# E77whistle.net
KiCad netlist of a schematic drawn in Altium Designer
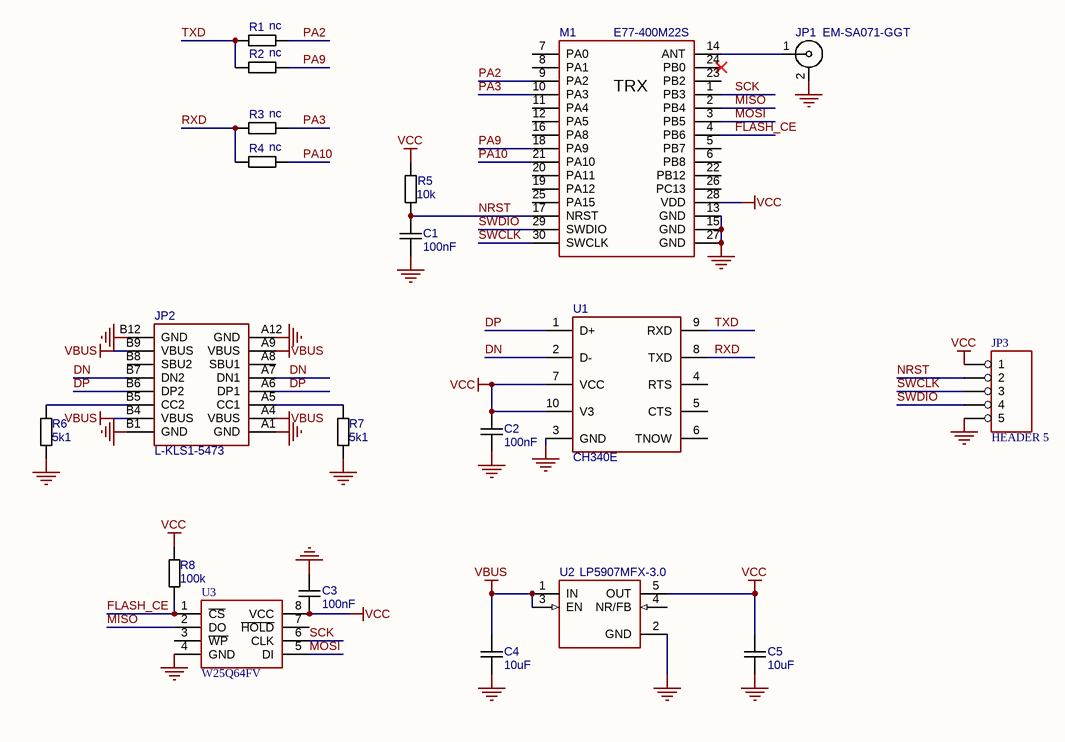
[diagram p0: E77whistle.SchDoc]

(export (version "E")
  (design (tool "Eeschema 10.0.6"))
  (components
    (comp (ref "C1")
      (value "100nF")
      (footprint "C-0603")
      (fields (field (name "VOLTAGE") "50V"))
      (libsource (lib "Passive") (part "CAPN"))
    )
    (comp (ref "C2")
      (value "100nF")
      (footprint "C-0603")
      (fields (field (name "VOLTAGE") "50V"))
      (libsource (lib "Passive") (part "CAPN"))
    )
    (comp (ref "C3")
      (value "100nF")
      (footprint "C-0603")
      (fields (field (name "VOLTAGE") "50V"))
      (libsource (lib "Passive") (part "CAPN"))
    )
    (comp (ref "C4")
      (value "10uF")
      (footprint "C-0805")
      (fields (field (name "VOLTAGE") "50V"))
      (libsource (lib "Passive") (part "CAPN"))
    )
    (comp (ref "C5")
      (value "10uF")
      (footprint "C-0805")
      (fields (field (name "VOLTAGE") "50V"))
      (libsource (lib "Passive") (part "CAPN"))
    )
    (comp (ref "JP1")
      (value "EM-SA071-GGT")
      (footprint "SMA_F_EDGE")
      (description "SMA Female R/A PCB Mount")
      (libsource (lib "Connectors") (part "SMA"))
    )
    (comp (ref "JP2")
      (value "L-KLS1-5473")
      (footprint "L-KLS1-5473")
      (libsource (lib "Connectors") (part "L-KLS1-5473"))
    )
    (comp (ref "JP3")
      (value "HEADER 5")
      (footprint "PLS1-5_SMD")
      (libsource (lib "Connectors") (part "HEADER 5"))
    )
    (comp (ref "M1")
      (value "E77-400M22S")
      (footprint "E77XX-M22")
      (libsource (lib "RFmodules") (part "E77-400M22S"))
    )
    (comp (ref "R1") (value "nc") (footprint "R-0603") (libsource (lib "Passive") (part "RES")))
    (comp (ref "R2") (value "nc") (footprint "R-0603") (libsource (lib "Passive") (part "RES")))
    (comp (ref "R3") (value "nc") (footprint "R-0603") (libsource (lib "Passive") (part "RES")))
    (comp (ref "R4") (value "nc") (footprint "R-0603") (libsource (lib "Passive") (part "RES")))
    (comp (ref "R5") (value "10k") (footprint "R-0603") (libsource (lib "") (part "RES_1")))
    (comp (ref "R6") (value "5k1") (footprint "R-0603") (libsource (lib "") (part "RES_2")))
    (comp (ref "R7") (value "5k1") (footprint "R-0603") (libsource (lib "") (part "RES_2")))
    (comp (ref "R8") (value "100k") (footprint "R-0603") (libsource (lib "") (part "RES_1")))
    (comp (ref "U1") (value "CH340E") (footprint "MSOP-10") (libsource (lib "ICs") (part "CH340E")))
    (comp (ref "U2")
      (value "LP5907MFX-3.0")
      (footprint "SOT-23-5")
      (description "250mA Low-Dropout Regulator")
      (libsource (lib "ICs") (part "LP5907"))
    )
    (comp (ref "U3") (value "W25Q64FV") (footprint "SO-8") (libsource (lib "ICs") (part "W25Q64FV")))
  )
  (nets
    (net (code "1") (name "/DN") (class "Default")
      (node (ref "JP2") (pin "A7") (pinfunction "DN1_A7") (pintype "passive"))
      (node (ref "JP2") (pin "B7") (pinfunction "DN2_B7") (pintype "passive"))
      (node (ref "U1") (pin "2") (pinfunction "D-_2") (pintype "passive"))
    )
    (net (code "2") (name "/DP") (class "Default")
      (node (ref "JP2") (pin "A6") (pinfunction "DP1_A6") (pintype "passive"))
      (node (ref "JP2") (pin "B6") (pinfunction "DP2_B6") (pintype "passive"))
      (node (ref "U1") (pin "1") (pinfunction "D+_1") (pintype "passive"))
    )
    (net (code "3") (name "/FLASH_CE") (class "Default")
      (node (ref "M1") (pin "4") (pinfunction "PB6_4") (pintype "passive"))
      (node (ref "R8") (pin "1") (pinfunction "1_1") (pintype "passive"))
      (node (ref "U3") (pin "1") (pinfunction "~{CS}_1") (pintype "passive"))
    )
    (net (code "4") (name "/MISO") (class "Default")
      (node (ref "M1") (pin "2") (pinfunction "PB4_2") (pintype "passive"))
      (node (ref "U3") (pin "2") (pinfunction "DO_2") (pintype "passive"))
    )
    (net (code "5") (name "/MOSI") (class "Default")
      (node (ref "M1") (pin "3") (pinfunction "PB5_3") (pintype "passive"))
      (node (ref "U3") (pin "5") (pinfunction "DI_5") (pintype "passive"))
    )
    (net (code "6") (name "/NRST") (class "Default")
      (node (ref "C1") (pin "2") (pinfunction "2_2") (pintype "passive"))
      (node (ref "JP3") (pin "2") (pinfunction "2_2") (pintype "passive"))
      (node (ref "M1") (pin "17") (pinfunction "NRST_17") (pintype "passive"))
      (node (ref "R5") (pin "1") (pinfunction "1_1") (pintype "passive"))
    )
    (net (code "7") (name "/PA2") (class "Default")
      (node (ref "M1") (pin "9") (pinfunction "PA2_9") (pintype "passive"))
      (node (ref "R1") (pin "1") (pinfunction "1_1") (pintype "passive"))
    )
    (net (code "8") (name "/PA3") (class "Default")
      (node (ref "M1") (pin "10") (pinfunction "PA3_10") (pintype "passive"))
      (node (ref "R3") (pin "1") (pinfunction "1_1") (pintype "passive"))
    )
    (net (code "9") (name "/PA9") (class "Default")
      (node (ref "M1") (pin "18") (pinfunction "PA9_18") (pintype "passive"))
      (node (ref "R2") (pin "1") (pinfunction "1_1") (pintype "passive"))
    )
    (net (code "10") (name "/PA10") (class "Default")
      (node (ref "M1") (pin "21") (pinfunction "PA10_21") (pintype "passive"))
      (node (ref "R4") (pin "1") (pinfunction "1_1") (pintype "passive"))
    )
    (net (code "11") (name "/RXD") (class "Default")
      (node (ref "R3") (pin "2") (pinfunction "2_2") (pintype "passive"))
      (node (ref "R4") (pin "2") (pinfunction "2_2") (pintype "passive"))
      (node (ref "U1") (pin "8") (pinfunction "TXD_8") (pintype "passive"))
    )
    (net (code "12") (name "/SCK") (class "Default")
      (node (ref "M1") (pin "1") (pinfunction "PB3_1") (pintype "passive"))
      (node (ref "U3") (pin "6") (pinfunction "CLK_6") (pintype "passive"))
    )
    (net (code "13") (name "/SWCLK") (class "Default")
      (node (ref "JP3") (pin "3") (pinfunction "3_3") (pintype "passive"))
      (node (ref "M1") (pin "30") (pinfunction "SWCLK_30") (pintype "passive"))
    )
    (net (code "14") (name "/SWDIO") (class "Default")
      (node (ref "JP3") (pin "4") (pinfunction "4_4") (pintype "passive"))
      (node (ref "M1") (pin "29") (pinfunction "SWDIO_29") (pintype "passive"))
    )
    (net (code "15") (name "/TXD") (class "Default")
      (node (ref "R1") (pin "2") (pinfunction "2_2") (pintype "passive"))
      (node (ref "R2") (pin "2") (pinfunction "2_2") (pintype "passive"))
      (node (ref "U1") (pin "9") (pinfunction "RXD_9") (pintype "passive"))
    )
    (net (code "16") (name "GND") (class "Default")
      (node (ref "C1") (pin "1") (pinfunction "1_1") (pintype "passive"))
      (node (ref "C2") (pin "1") (pinfunction "1_1") (pintype "passive"))
      (node (ref "C3") (pin "1") (pinfunction "1_1") (pintype "passive"))
      (node (ref "C4") (pin "2") (pinfunction "2_2") (pintype "passive"))
      (node (ref "C5") (pin "2") (pinfunction "2_2") (pintype "passive"))
      (node (ref "JP1") (pin "2") (pinfunction "2_2") (pintype "passive"))
      (node (ref "JP2") (pin "A1") (pinfunction "GND_A1") (pintype "passive"))
      (node (ref "JP2") (pin "A12") (pinfunction "GND_A12") (pintype "passive"))
      (node (ref "JP2") (pin "B1") (pinfunction "GND_B1") (pintype "passive"))
      (node (ref "JP2") (pin "B12") (pinfunction "GND_B12") (pintype "passive"))
      (node (ref "JP3") (pin "5") (pinfunction "5_5") (pintype "passive"))
      (node (ref "M1") (pin "13") (pinfunction "GND_13") (pintype "passive"))
      (node (ref "M1") (pin "15") (pinfunction "GND_15") (pintype "passive"))
      (node (ref "M1") (pin "27") (pinfunction "GND_27") (pintype "passive"))
      (node (ref "R6") (pin "2") (pinfunction "2_2") (pintype "passive"))
      (node (ref "R7") (pin "2") (pinfunction "2_2") (pintype "passive"))
      (node (ref "U1") (pin "3") (pinfunction "GND_3") (pintype "passive"))
      (node (ref "U2") (pin "2") (pinfunction "GND_2") (pintype "power_in"))
      (node (ref "U3") (pin "4") (pinfunction "GND_4") (pintype "passive"))
    )
    (net (code "17") (name "Net-(JP2-CC1)") (class "Default")
      (node (ref "JP2") (pin "A5") (pinfunction "CC1_A5") (pintype "passive"))
      (node (ref "R7") (pin "1") (pinfunction "1_1") (pintype "passive"))
    )
    (net (code "18") (name "Net-(JP2-CC2)") (class "Default")
      (node (ref "JP2") (pin "B5") (pinfunction "CC2_B5") (pintype "passive"))
      (node (ref "R6") (pin "1") (pinfunction "1_1") (pintype "passive"))
    )
    (net (code "19") (name "Net-(M1-ANT)") (class "Default")
      (node (ref "JP1") (pin "1") (pinfunction "1_1") (pintype "passive"))
      (node (ref "M1") (pin "14") (pinfunction "ANT_14") (pintype "passive"))
    )
    (net (code "20") (name "VBUS") (class "Default")
      (node (ref "C4") (pin "1") (pinfunction "1_1") (pintype "passive"))
      (node (ref "JP2") (pin "A4") (pinfunction "VBUS_A4") (pintype "passive"))
      (node (ref "JP2") (pin "A9") (pinfunction "VBUS_A9") (pintype "passive"))
      (node (ref "JP2") (pin "B4") (pinfunction "VBUS_B4") (pintype "passive"))
      (node (ref "JP2") (pin "B9") (pinfunction "VBUS_B9") (pintype "passive"))
      (node (ref "U2") (pin "1") (pinfunction "IN_1") (pintype "power_in"))
      (node (ref "U2") (pin "3") (pinfunction "EN_3") (pintype "input"))
    )
    (net (code "21") (name "VCC") (class "Default")
      (node (ref "C2") (pin "2") (pinfunction "2_2") (pintype "passive"))
      (node (ref "C3") (pin "2") (pinfunction "2_2") (pintype "passive"))
      (node (ref "C5") (pin "1") (pinfunction "1_1") (pintype "passive"))
      (node (ref "JP3") (pin "1") (pinfunction "1_1") (pintype "passive"))
      (node (ref "M1") (pin "28") (pinfunction "VDD_28") (pintype "passive"))
      (node (ref "R5") (pin "2") (pinfunction "2_2") (pintype "passive"))
      (node (ref "R8") (pin "2") (pinfunction "2_2") (pintype "passive"))
      (node (ref "U1") (pin "10") (pinfunction "V3_10") (pintype "passive"))
      (node (ref "U1") (pin "7") (pinfunction "VCC_7") (pintype "passive"))
      (node (ref "U2") (pin "5") (pinfunction "OUT_5") (pintype "power_in"))
      (node (ref "U3") (pin "8") (pinfunction "VCC_8") (pintype "passive"))
    )
    (net (code "22") (name "VSS") (class "Default")
      (node (ref "JP2") (pin "17") (pinfunction "VSS_17") (pintype "power_in"))
    )
    (net (code "23") (name "unconnected-(JP2-SBU1-PadA8)") (class "Default")
      (node (ref "JP2") (pin "A8") (pinfunction "SBU1_A8") (pintype "passive"))
    )
    (net (code "24") (name "unconnected-(JP2-SBU2-PadB8)") (class "Default")
      (node (ref "JP2") (pin "B8") (pinfunction "SBU2_B8") (pintype "passive"))
    )
    (net (code "25") (name "unconnected-(M1-PA0-Pad7)") (class "Default")
      (node (ref "M1") (pin "7") (pinfunction "PA0_7") (pintype "passive"))
    )
    (net (code "26") (name "unconnected-(M1-PA1-Pad8)") (class "Default")
      (node (ref "M1") (pin "8") (pinfunction "PA1_8") (pintype "passive"))
    )
    (net (code "27") (name "unconnected-(M1-PA4-Pad11)") (class "Default")
      (node (ref "M1") (pin "11") (pinfunction "PA4_11") (pintype "passive"))
    )
    (net (code "28") (name "unconnected-(M1-PA5-Pad12)") (class "Default")
      (node (ref "M1") (pin "12") (pinfunction "PA5_12") (pintype "passive"))
    )
    (net (code "29") (name "unconnected-(M1-PA8-Pad16)") (class "Default")
      (node (ref "M1") (pin "16") (pinfunction "PA8_16") (pintype "passive"))
    )
    (net (code "30") (name "unconnected-(M1-PA11-Pad20)") (class "Default")
      (node (ref "M1") (pin "20") (pinfunction "PA11_20") (pintype "passive"))
    )
    (net (code "31") (name "unconnected-(M1-PA12-Pad19)") (class "Default")
      (node (ref "M1") (pin "19") (pinfunction "PA12_19") (pintype "passive"))
    )
    (net (code "32") (name "unconnected-(M1-PA15-Pad25)") (class "Default")
      (node (ref "M1") (pin "25") (pinfunction "PA15_25") (pintype "passive"))
    )
    (net (code "33") (name "unconnected-(M1-PB0-Pad24)") (class "Default")
      (node (ref "M1") (pin "24") (pinfunction "PB0_24") (pintype "passive+no_connect"))
    )
    (net (code "34") (name "unconnected-(M1-PB2-Pad23)") (class "Default")
      (node (ref "M1") (pin "23") (pinfunction "PB2_23") (pintype "passive"))
    )
    (net (code "35") (name "unconnected-(M1-PB7-Pad5)") (class "Default")
      (node (ref "M1") (pin "5") (pinfunction "PB7_5") (pintype "passive"))
    )
    (net (code "36") (name "unconnected-(M1-PB8-Pad6)") (class "Default")
      (node (ref "M1") (pin "6") (pinfunction "PB8_6") (pintype "passive"))
    )
    (net (code "37") (name "unconnected-(M1-PB12-Pad22)") (class "Default")
      (node (ref "M1") (pin "22") (pinfunction "PB12_22") (pintype "passive"))
    )
    (net (code "38") (name "unconnected-(M1-PC13-Pad26)") (class "Default")
      (node (ref "M1") (pin "26") (pinfunction "PC13_26") (pintype "passive"))
    )
    (net (code "39") (name "unconnected-(U1-CTS-Pad5)") (class "Default")
      (node (ref "U1") (pin "5") (pinfunction "CTS_5") (pintype "passive"))
    )
    (net (code "40") (name "unconnected-(U1-RTS-Pad4)") (class "Default")
      (node (ref "U1") (pin "4") (pinfunction "RTS_4") (pintype "passive"))
    )
    (net (code "41") (name "unconnected-(U1-TNOW-Pad6)") (class "Default")
      (node (ref "U1") (pin "6") (pinfunction "TNOW_6") (pintype "passive"))
    )
    (net (code "42") (name "unconnected-(U2-NR{slash}FB-Pad4)") (class "Default")
      (node (ref "U2") (pin "4") (pinfunction "NR/FB_4") (pintype "input"))
    )
    (net (code "43") (name "unconnected-(U3-~{HOLD}-Pad7)") (class "Default")
      (node (ref "U3") (pin "7") (pinfunction "~{HOLD}_7") (pintype "passive"))
    )
    (net (code "44") (name "unconnected-(U3-~{WP}-Pad3)") (class "Default")
      (node (ref "U3") (pin "3") (pinfunction "~{WP}_3") (pintype "passive"))
    )
  )
)
